# node.net
KiCad netlist of a schematic drawn in EAGLE
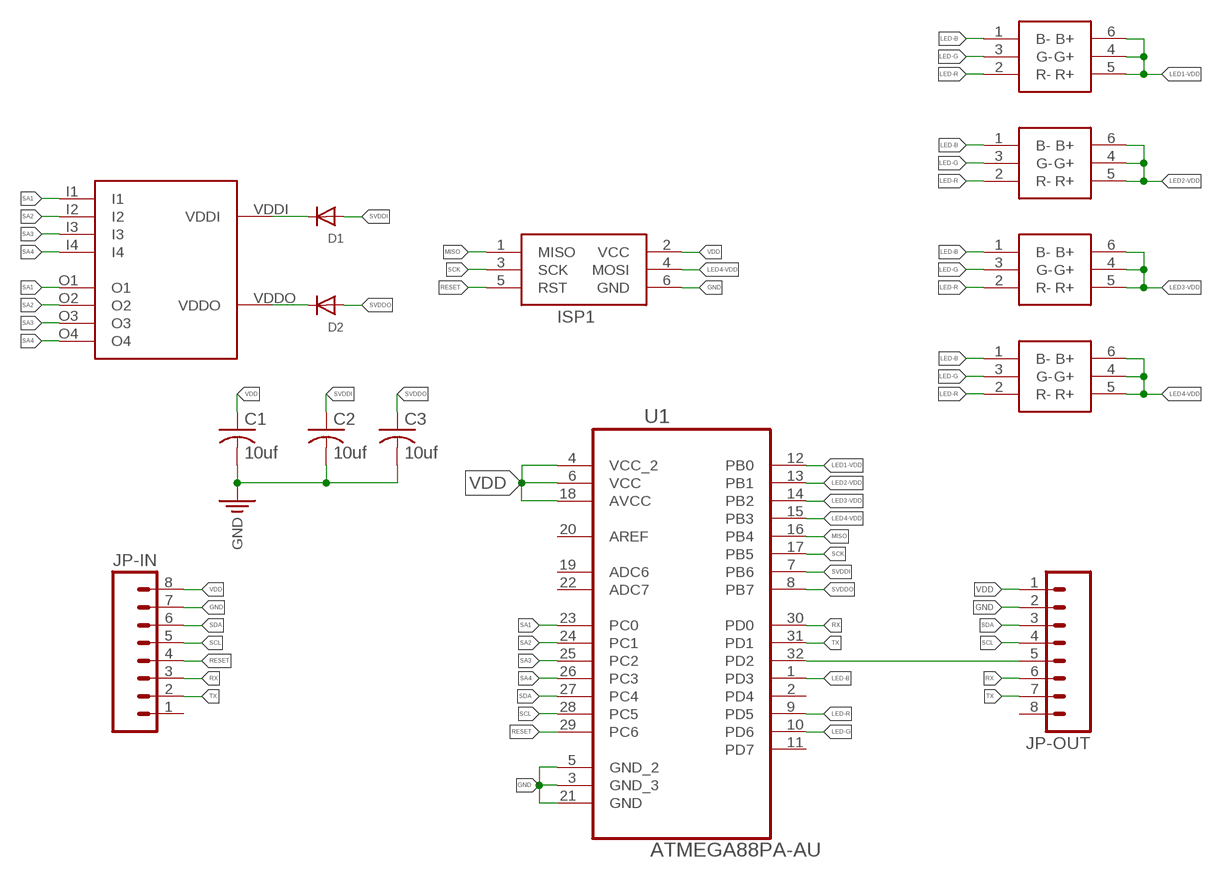
[diagram p0: schematic, sheet 1]

(export (version "E")
  (design (tool "Eeschema 10.0.6"))
  (components
    (comp (ref "C1")
      (value "10uf")
      (footprint "eagle-import:C0805K")
      (libsource (lib "eagle-import") (part "C-USC0805K"))
    )
    (comp (ref "C2")
      (value "10uf")
      (footprint "eagle-import:C0805K")
      (libsource (lib "eagle-import") (part "C-USC0805K"))
    )
    (comp (ref "C3")
      (value "10uf")
      (footprint "eagle-import:C0805K")
      (libsource (lib "eagle-import") (part "C-USC0805K"))
    )
    (comp (ref "D1")
      (value "DIODESOD-323F")
      (footprint "eagle-import:SOD-323F")
      (libsource (lib "eagle-import") (part "DIODESOD-323F"))
    )
    (comp (ref "D2")
      (value "DIODESOD-323F")
      (footprint "eagle-import:SOD-323F")
      (libsource (lib "eagle-import") (part "DIODESOD-323F"))
    )
    (comp (ref "ISP1")
      (value "AVRISP-6")
      (footprint "eagle-import:AVRISP")
      (libsource (lib "eagle-import") (part "AVRISP-6"))
    )
    (comp (ref "JP-IN")
      (value "M08LONGPADS")
      (footprint "eagle-import:1X08_LONGPADS")
      (libsource (lib "eagle-import") (part "M08LONGPADS"))
    )
    (comp (ref "JP-OUT")
      (value "M08LONGPADS")
      (footprint "eagle-import:1X08_LONGPADS")
      (libsource (lib "eagle-import") (part "M08LONGPADS"))
    )
    (comp (ref "LED1")
      (value "SMT-RGB-6PLCC")
      (footprint "eagle-import:SMT-RGB-6PLCC")
      (libsource (lib "eagle-import") (part "SMT-RGB-6PLCC"))
    )
    (comp (ref "LED2")
      (value "SMT-RGB-6PLCC")
      (footprint "eagle-import:SMT-RGB-6PLCC")
      (libsource (lib "eagle-import") (part "SMT-RGB-6PLCC"))
    )
    (comp (ref "LED3")
      (value "SMT-RGB-6PLCC")
      (footprint "eagle-import:SMT-RGB-6PLCC")
      (libsource (lib "eagle-import") (part "SMT-RGB-6PLCC"))
    )
    (comp (ref "LED4")
      (value "SMT-RGB-6PLCC")
      (footprint "eagle-import:SMT-RGB-6PLCC")
      (libsource (lib "eagle-import") (part "SMT-RGB-6PLCC"))
    )
    (comp (ref "U$2")
      (value "SPS8-0.0.1")
      (footprint "eagle-import:SPS8-0.0.1")
      (libsource (lib "eagle-import") (part "SPS8-0.0.1"))
    )
    (comp (ref "U1")
      (value "ATMEGA88PA-AU")
      (footprint "eagle-import:QFP80P900X900X120-32N")
      (libsource (lib "eagle-import") (part "ATMEGA88PA-AU"))
    )
  )
  (nets
    (net (code "1") (name "GND") (class "Default")
      (node (ref "C1") (pin "2") (pinfunction "2_2") (pintype "passive"))
      (node (ref "C2") (pin "2") (pinfunction "2_2") (pintype "passive"))
      (node (ref "C3") (pin "2") (pinfunction "2_2") (pintype "passive"))
      (node (ref "ISP1") (pin "6") (pinfunction "GND_6") (pintype "power_in"))
      (node (ref "JP-IN") (pin "7") (pinfunction "7_7") (pintype "passive"))
      (node (ref "JP-OUT") (pin "2") (pinfunction "2_2") (pintype "passive"))
      (node (ref "U1") (pin "21") (pinfunction "GND_21") (pintype "passive"))
      (node (ref "U1") (pin "3") (pinfunction "GND_3_3") (pintype "passive"))
      (node (ref "U1") (pin "5") (pinfunction "GND_2_5") (pintype "passive"))
    )
    (net (code "2") (name "LED-B") (class "Default")
      (node (ref "LED1") (pin "1") (pinfunction "B-_1") (pintype "bidirectional"))
      (node (ref "LED2") (pin "1") (pinfunction "B-_1") (pintype "bidirectional"))
      (node (ref "LED3") (pin "1") (pinfunction "B-_1") (pintype "bidirectional"))
      (node (ref "LED4") (pin "1") (pinfunction "B-_1") (pintype "bidirectional"))
      (node (ref "U1") (pin "1") (pinfunction "PD3_1") (pintype "bidirectional"))
    )
    (net (code "3") (name "LED-G") (class "Default")
      (node (ref "LED1") (pin "3") (pinfunction "G-_3") (pintype "bidirectional"))
      (node (ref "LED2") (pin "3") (pinfunction "G-_3") (pintype "bidirectional"))
      (node (ref "LED3") (pin "3") (pinfunction "G-_3") (pintype "bidirectional"))
      (node (ref "LED4") (pin "3") (pinfunction "G-_3") (pintype "bidirectional"))
      (node (ref "U1") (pin "10") (pinfunction "PD6_10") (pintype "bidirectional"))
    )
    (net (code "4") (name "LED-R") (class "Default")
      (node (ref "LED1") (pin "2") (pinfunction "R-_2") (pintype "bidirectional"))
      (node (ref "LED2") (pin "2") (pinfunction "R-_2") (pintype "bidirectional"))
      (node (ref "LED3") (pin "2") (pinfunction "R-_2") (pintype "bidirectional"))
      (node (ref "LED4") (pin "2") (pinfunction "R-_2") (pintype "bidirectional"))
      (node (ref "U1") (pin "9") (pinfunction "PD5_9") (pintype "bidirectional"))
    )
    (net (code "5") (name "LED1-VDD") (class "Default")
      (node (ref "LED1") (pin "4") (pinfunction "G+_4") (pintype "bidirectional"))
      (node (ref "LED1") (pin "5") (pinfunction "R+_5") (pintype "bidirectional"))
      (node (ref "LED1") (pin "6") (pinfunction "B+_6") (pintype "bidirectional"))
      (node (ref "U1") (pin "12") (pinfunction "PB0_12") (pintype "bidirectional"))
    )
    (net (code "6") (name "LED2-VDD") (class "Default")
      (node (ref "LED2") (pin "4") (pinfunction "G+_4") (pintype "bidirectional"))
      (node (ref "LED2") (pin "5") (pinfunction "R+_5") (pintype "bidirectional"))
      (node (ref "LED2") (pin "6") (pinfunction "B+_6") (pintype "bidirectional"))
      (node (ref "U1") (pin "13") (pinfunction "PB1_13") (pintype "bidirectional"))
    )
    (net (code "7") (name "LED3-VDD") (class "Default")
      (node (ref "LED3") (pin "4") (pinfunction "G+_4") (pintype "bidirectional"))
      (node (ref "LED3") (pin "5") (pinfunction "R+_5") (pintype "bidirectional"))
      (node (ref "LED3") (pin "6") (pinfunction "B+_6") (pintype "bidirectional"))
      (node (ref "U1") (pin "14") (pinfunction "PB2_14") (pintype "bidirectional"))
    )
    (net (code "8") (name "LED4-VDD") (class "Default")
      (node (ref "ISP1") (pin "4") (pinfunction "MOSI_4") (pintype "output"))
      (node (ref "LED4") (pin "4") (pinfunction "G+_4") (pintype "bidirectional"))
      (node (ref "LED4") (pin "5") (pinfunction "R+_5") (pintype "bidirectional"))
      (node (ref "LED4") (pin "6") (pinfunction "B+_6") (pintype "bidirectional"))
      (node (ref "U1") (pin "15") (pinfunction "PB3_15") (pintype "bidirectional"))
    )
    (net (code "9") (name "MISO") (class "Default")
      (node (ref "ISP1") (pin "1") (pinfunction "MISO_1") (pintype "input"))
      (node (ref "U1") (pin "16") (pinfunction "PB4_16") (pintype "bidirectional"))
    )
    (net (code "10") (name "Net-(D1-PadC)") (class "Default")
      (node (ref "D1") (pin "C") (pinfunction "C_C") (pintype "passive"))
      (node (ref "U$2") (pin "VDDI") (pinfunction "VDDI_VDDI") (pintype "bidirectional"))
    )
    (net (code "11") (name "Net-(D2-PadC)") (class "Default")
      (node (ref "D2") (pin "C") (pinfunction "C_C") (pintype "passive"))
      (node (ref "U$2") (pin "VDDO") (pinfunction "VDDO_VDDO") (pintype "bidirectional"))
    )
    (net (code "12") (name "Net-(U1-PD2)") (class "Default")
      (node (ref "JP-OUT") (pin "5") (pinfunction "5_5") (pintype "passive"))
      (node (ref "U1") (pin "32") (pinfunction "PD2_32") (pintype "bidirectional"))
    )
    (net (code "13") (name "RESET") (class "Default")
      (node (ref "ISP1") (pin "5") (pinfunction "RST_5") (pintype "output"))
      (node (ref "JP-IN") (pin "4") (pinfunction "4_4") (pintype "passive"))
      (node (ref "U1") (pin "29") (pinfunction "PC6_29") (pintype "bidirectional"))
    )
    (net (code "14") (name "RX") (class "Default")
      (node (ref "JP-IN") (pin "3") (pinfunction "3_3") (pintype "passive"))
      (node (ref "JP-OUT") (pin "6") (pinfunction "6_6") (pintype "passive"))
      (node (ref "U1") (pin "30") (pinfunction "PD0_30") (pintype "bidirectional"))
    )
    (net (code "15") (name "SA1") (class "Default")
      (node (ref "U$2") (pin "I1") (pinfunction "I1_I1") (pintype "bidirectional"))
      (node (ref "U$2") (pin "O1") (pinfunction "O1_O1") (pintype "bidirectional"))
      (node (ref "U1") (pin "23") (pinfunction "PC0_23") (pintype "bidirectional"))
    )
    (net (code "16") (name "SA2") (class "Default")
      (node (ref "U$2") (pin "I2") (pinfunction "I2_I2") (pintype "bidirectional"))
      (node (ref "U$2") (pin "O2") (pinfunction "O2_O2") (pintype "bidirectional"))
      (node (ref "U1") (pin "24") (pinfunction "PC1_24") (pintype "bidirectional"))
    )
    (net (code "17") (name "SA3") (class "Default")
      (node (ref "U$2") (pin "I3") (pinfunction "I3_I3") (pintype "bidirectional"))
      (node (ref "U$2") (pin "O3") (pinfunction "O3_O3") (pintype "bidirectional"))
      (node (ref "U1") (pin "25") (pinfunction "PC2_25") (pintype "bidirectional"))
    )
    (net (code "18") (name "SA4") (class "Default")
      (node (ref "U$2") (pin "I4") (pinfunction "I4_I4") (pintype "bidirectional"))
      (node (ref "U$2") (pin "O4") (pinfunction "O4_O4") (pintype "bidirectional"))
      (node (ref "U1") (pin "26") (pinfunction "PC3_26") (pintype "bidirectional"))
    )
    (net (code "19") (name "SCK") (class "Default")
      (node (ref "ISP1") (pin "3") (pinfunction "SCK_3") (pintype "output"))
      (node (ref "U1") (pin "17") (pinfunction "PB5_17") (pintype "bidirectional"))
    )
    (net (code "20") (name "SCL") (class "Default")
      (node (ref "JP-IN") (pin "5") (pinfunction "5_5") (pintype "passive"))
      (node (ref "JP-OUT") (pin "4") (pinfunction "4_4") (pintype "passive"))
      (node (ref "U1") (pin "28") (pinfunction "PC5_28") (pintype "bidirectional"))
    )
    (net (code "21") (name "SDA") (class "Default")
      (node (ref "JP-IN") (pin "6") (pinfunction "6_6") (pintype "passive"))
      (node (ref "JP-OUT") (pin "3") (pinfunction "3_3") (pintype "passive"))
      (node (ref "U1") (pin "27") (pinfunction "PC4_27") (pintype "bidirectional"))
    )
    (net (code "22") (name "SVDDI") (class "Default")
      (node (ref "C2") (pin "1") (pinfunction "1_1") (pintype "passive"))
      (node (ref "D1") (pin "A") (pinfunction "A_A") (pintype "passive"))
      (node (ref "U1") (pin "7") (pinfunction "PB6_7") (pintype "bidirectional"))
    )
    (net (code "23") (name "SVDDO") (class "Default")
      (node (ref "C3") (pin "1") (pinfunction "1_1") (pintype "passive"))
      (node (ref "D2") (pin "A") (pinfunction "A_A") (pintype "passive"))
      (node (ref "U1") (pin "8") (pinfunction "PB7_8") (pintype "bidirectional"))
    )
    (net (code "24") (name "TX") (class "Default")
      (node (ref "JP-IN") (pin "2") (pinfunction "2_2") (pintype "passive"))
      (node (ref "JP-OUT") (pin "7") (pinfunction "7_7") (pintype "passive"))
      (node (ref "U1") (pin "31") (pinfunction "PD1_31") (pintype "bidirectional"))
    )
    (net (code "25") (name "VDD") (class "Default")
      (node (ref "C1") (pin "1") (pinfunction "1_1") (pintype "passive"))
      (node (ref "ISP1") (pin "2") (pinfunction "VCC_2") (pintype "power_in"))
      (node (ref "JP-IN") (pin "8") (pinfunction "8_8") (pintype "passive"))
      (node (ref "JP-OUT") (pin "1") (pinfunction "1_1") (pintype "passive"))
      (node (ref "U1") (pin "18") (pinfunction "AVCC_18") (pintype "power_in"))
      (node (ref "U1") (pin "4") (pinfunction "VCC_2_4") (pintype "power_in"))
      (node (ref "U1") (pin "6") (pinfunction "VCC_6") (pintype "power_in"))
    )
    (net (code "26") (name "unconnected-(JP-IN-Pad1)") (class "Default")
      (node (ref "JP-IN") (pin "1") (pinfunction "1_1") (pintype "passive"))
    )
    (net (code "27") (name "unconnected-(JP-OUT-Pad8)") (class "Default")
      (node (ref "JP-OUT") (pin "8") (pinfunction "8_8") (pintype "passive"))
    )
    (net (code "28") (name "unconnected-(U1-ADC6-Pad19)") (class "Default")
      (node (ref "U1") (pin "19") (pinfunction "ADC6_19") (pintype "input"))
    )
    (net (code "29") (name "unconnected-(U1-ADC7-Pad22)") (class "Default")
      (node (ref "U1") (pin "22") (pinfunction "ADC7_22") (pintype "input"))
    )
    (net (code "30") (name "unconnected-(U1-AREF-Pad20)") (class "Default")
      (node (ref "U1") (pin "20") (pinfunction "AREF_20") (pintype "input"))
    )
    (net (code "31") (name "unconnected-(U1-PD4-Pad2)") (class "Default")
      (node (ref "U1") (pin "2") (pinfunction "PD4_2") (pintype "bidirectional"))
    )
    (net (code "32") (name "unconnected-(U1-PD7-Pad11)") (class "Default")
      (node (ref "U1") (pin "11") (pinfunction "PD7_11") (pintype "bidirectional"))
    )
  )
)
